# Display.net
KiCad netlist of a schematic drawn in Altium Designer
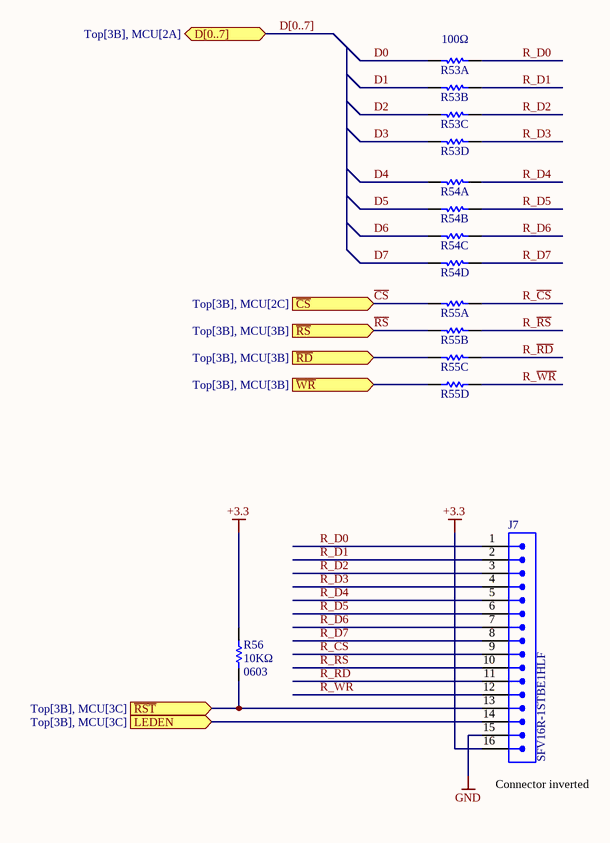
[diagram p0: Display.SchDoc]

(export (version "E")
  (design (tool "Eeschema 10.0.6"))
  (components
    (comp (ref "J7")
      (value "SFV16R-1STBE1HLF")
      (footprint "FFC16POS")
      (description "16 Position FFC, FPC Connector Contacts, Bottom 0.020\" (0.50mm) Surface Mount, Right Angle")
      (libsource (lib "Amphenol ICC (FCI)") (part "SFV16R-1STBE1HLF"))
    )
    (comp (ref "R53")
      (value "100Ω")
      (footprint "1206")
      (fields
        (field (name "TOLERANCE") "±5%")
        (field (name "POWER") "62.5mW")
        (field (name "Comment") "YC164-JR-07100RL")
      )
      (libsource (lib "YAGEO") (part "YC164-JR-07100RL"))
    )
    (comp (ref "R54")
      (value "YC164-JR-07100RL")
      (footprint "1206")
      (fields (field (name "TOLERANCE") "±5%") (field (name "POWER") "62.5mW"))
      (libsource (lib "YAGEO") (part "YC164-JR-07100RL"))
    )
    (comp (ref "R55")
      (value "YC164-JR-07100RL")
      (footprint "1206")
      (fields (field (name "TOLERANCE") "±5%") (field (name "POWER") "62.5mW"))
      (libsource (lib "YAGEO") (part "YC164-JR-07100RL"))
    )
    (comp (ref "R56")
      (value "10KΩ")
      (footprint "0603")
      (description "10 kOhms ±1% 0.1W, 1/10W Chip Resistor 0603 (1608 Metric) Automotive AEC-Q200 Thick Film")
      (fields (field (name "CASE") "0603") (field (name "TOLERANCE") "1%") (field (name "POWER") "0.1W"))
      (libsource (lib "Stackpole Electronics Inc") (part "RMCF0603FG10K0"))
    )
  )
  (nets
    (net (code "1") (name "+3.3") (class "Default")
      (node (ref "J7") (pin "16") (pinfunction "16_16") (pintype "passive"))
      (node (ref "R56") (pin "2") (pinfunction "2_2") (pintype "passive"))
    )
    (net (code "2") (name "/D0") (class "Default")
      (node (ref "R53") (pin "8") (pinfunction "8_8") (pintype "passive"))
    )
    (net (code "3") (name "/D1") (class "Default")
      (node (ref "R53") (pin "7") (pinfunction "7_7") (pintype "passive"))
    )
    (net (code "4") (name "/D2") (class "Default")
      (node (ref "R53") (pin "6") (pinfunction "6_6") (pintype "passive"))
    )
    (net (code "5") (name "/D3") (class "Default")
      (node (ref "R53") (pin "5") (pinfunction "5_5") (pintype "passive"))
    )
    (net (code "6") (name "/D4") (class "Default")
      (node (ref "R54") (pin "8") (pinfunction "8_8") (pintype "passive"))
    )
    (net (code "7") (name "/D5") (class "Default")
      (node (ref "R54") (pin "7") (pinfunction "7_7") (pintype "passive"))
    )
    (net (code "8") (name "/D6") (class "Default")
      (node (ref "R54") (pin "6") (pinfunction "6_6") (pintype "passive"))
    )
    (net (code "9") (name "/D7") (class "Default")
      (node (ref "R54") (pin "5") (pinfunction "5_5") (pintype "passive"))
    )
    (net (code "11") (name "/LEDEN") (class "Default")
      (node (ref "J7") (pin "14") (pinfunction "14_14") (pintype "passive"))
    )
    (net (code "12") (name "/R_D0") (class "Default")
      (node (ref "J7") (pin "1") (pinfunction "1_1") (pintype "passive"))
      (node (ref "R53") (pin "1") (pinfunction "1_1") (pintype "passive"))
    )
    (net (code "13") (name "/R_D1") (class "Default")
      (node (ref "J7") (pin "2") (pinfunction "2_2") (pintype "passive"))
      (node (ref "R53") (pin "2") (pinfunction "2_2") (pintype "passive"))
    )
    (net (code "14") (name "/R_D2") (class "Default")
      (node (ref "J7") (pin "3") (pinfunction "3_3") (pintype "passive"))
      (node (ref "R53") (pin "3") (pinfunction "3_3") (pintype "passive"))
    )
    (net (code "15") (name "/R_D3") (class "Default")
      (node (ref "J7") (pin "4") (pinfunction "4_4") (pintype "passive"))
      (node (ref "R53") (pin "4") (pinfunction "4_4") (pintype "passive"))
    )
    (net (code "16") (name "/R_D4") (class "Default")
      (node (ref "J7") (pin "5") (pinfunction "5_5") (pintype "passive"))
      (node (ref "R54") (pin "1") (pinfunction "1_1") (pintype "passive"))
    )
    (net (code "17") (name "/R_D5") (class "Default")
      (node (ref "J7") (pin "6") (pinfunction "6_6") (pintype "passive"))
      (node (ref "R54") (pin "2") (pinfunction "2_2") (pintype "passive"))
    )
    (net (code "18") (name "/R_D6") (class "Default")
      (node (ref "J7") (pin "7") (pinfunction "7_7") (pintype "passive"))
      (node (ref "R54") (pin "3") (pinfunction "3_3") (pintype "passive"))
    )
    (net (code "19") (name "/R_D7") (class "Default")
      (node (ref "J7") (pin "8") (pinfunction "8_8") (pintype "passive"))
      (node (ref "R54") (pin "4") (pinfunction "4_4") (pintype "passive"))
    )
    (net (code "20") (name "/R_~{CS}") (class "Default")
      (node (ref "J7") (pin "9") (pinfunction "9_9") (pintype "passive"))
      (node (ref "R55") (pin "1") (pinfunction "1_1") (pintype "passive"))
    )
    (net (code "21") (name "/R_~{RD}") (class "Default")
      (node (ref "J7") (pin "11") (pinfunction "11_11") (pintype "passive"))
      (node (ref "R55") (pin "3") (pinfunction "3_3") (pintype "passive"))
    )
    (net (code "22") (name "/R_~{RS}") (class "Default")
      (node (ref "J7") (pin "10") (pinfunction "10_10") (pintype "passive"))
      (node (ref "R55") (pin "2") (pinfunction "2_2") (pintype "passive"))
    )
    (net (code "23") (name "/R_~{WR}") (class "Default")
      (node (ref "J7") (pin "12") (pinfunction "12_12") (pintype "passive"))
      (node (ref "R55") (pin "4") (pinfunction "4_4") (pintype "passive"))
    )
    (net (code "24") (name "/~{CS}") (class "Default")
      (node (ref "R55") (pin "8") (pinfunction "8_8") (pintype "passive"))
    )
    (net (code "25") (name "/~{RD}") (class "Default")
      (node (ref "R55") (pin "6") (pinfunction "6_6") (pintype "passive"))
    )
    (net (code "26") (name "/~{RST}") (class "Default")
      (node (ref "J7") (pin "13") (pinfunction "13_13") (pintype "passive"))
      (node (ref "R56") (pin "1") (pinfunction "1_1") (pintype "passive"))
    )
    (net (code "27") (name "/~{RS}") (class "Default")
      (node (ref "R55") (pin "7") (pinfunction "7_7") (pintype "passive"))
    )
    (net (code "28") (name "/~{WR}") (class "Default")
      (node (ref "R55") (pin "5") (pinfunction "5_5") (pintype "passive"))
    )
    (net (code "29") (name "GND") (class "Default")
      (node (ref "J7") (pin "15") (pinfunction "15_15") (pintype "passive"))
    )
  )
)
